# Motor_Driver.net
KiCad netlist of a schematic drawn in Altium Designer
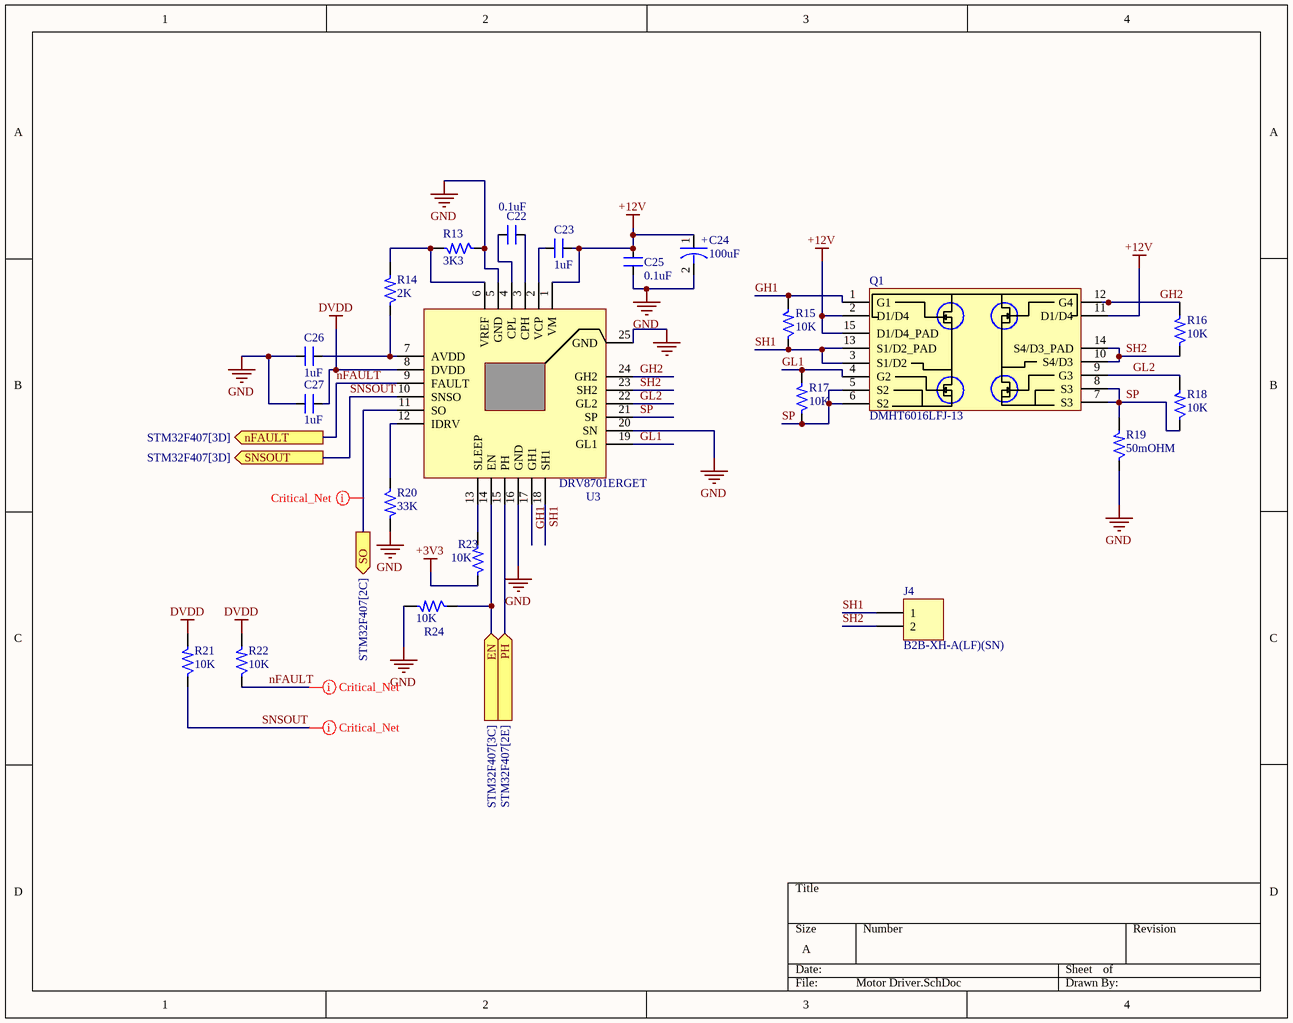
[diagram p0: Motor Driver.SchDoc]

(export (version "E")
  (design (tool "Eeschema 10.0.6"))
  (components
    (comp (ref "C22")
      (value "0.1uF")
      (footprint "CAP_0805")
      (description "0.1µF ±10% 50V Ceramic Capacitor X7R 0805 (2012 Metric)")
      (fields
        (field (name "MANUFACTURER") "Samsung")
        (field (name "MANUFACTURER PART NUMBER") "CL21B104KBCNNNC")
      )
      (libsource (lib "ESTEEMPCBLIB") (part "CAP_0.1uF-50V-10%-0805"))
    )
    (comp (ref "C23")
      (value "1uF")
      (footprint "CAP_0805")
      (description "1µF ±5% 50V Ceramic Capacitor X7R 0805 (2012 Metric)")
      (fields
        (field (name "MANUFACTURER") "Samsung")
        (field (name "MANUFACTURER PART NUMBER") "CC0805JKX7R9BB105")
      )
      (libsource (lib "ESTEEMPCBLIB") (part "CAP_1uF-50V-5%-0805"))
    )
    (comp (ref "C24")
      (value "100uF")
      (footprint "ACAP_P236_D305_H303_RAD")
      (description "100µF 25V Aluminum Electrolytic Capacitors Radial, Can - SMD 1000 Hrs @ 105°C")
      (fields
        (field (name "MANUFACTURER") "Nichicon")
        (field (name "MANUFACTURER PART NUMBER") "UWT1E101MCL1GS")
      )
      (libsource (lib "ESTEEMPCBLIB") (part "CAP-P_100uF-25V-20%-RAD"))
    )
    (comp (ref "C25")
      (value "0.1uF")
      (footprint "CAP_0805")
      (description "0.1µF ±10% 50V Ceramic Capacitor X7R 0805 (2012 Metric)")
      (fields
        (field (name "MANUFACTURER") "Samsung")
        (field (name "MANUFACTURER PART NUMBER") "CL21B104KBCNNNC")
      )
      (libsource (lib "ESTEEMPCBLIB") (part "CAP_0.1uF-50V-10%-0805"))
    )
    (comp (ref "C26")
      (value "1uF")
      (footprint "CAP_0805")
      (description "1µF ±5% 50V Ceramic Capacitor X7R 0805 (2012 Metric)")
      (fields
        (field (name "MANUFACTURER") "Samsung")
        (field (name "MANUFACTURER PART NUMBER") "CC0805JKX7R9BB105")
      )
      (libsource (lib "ESTEEMPCBLIB") (part "CAP_1uF-50V-5%-0805"))
    )
    (comp (ref "C27")
      (value "1uF")
      (footprint "CAP_0805")
      (description "1µF ±5% 50V Ceramic Capacitor X7R 0805 (2012 Metric)")
      (fields
        (field (name "MANUFACTURER") "Samsung")
        (field (name "MANUFACTURER PART NUMBER") "CC0805JKX7R9BB105")
      )
      (libsource (lib "ESTEEMPCBLIB") (part "CAP_1uF-50V-5%-0805"))
    )
    (comp (ref "J4")
      (value "B2B-XH-A(LF)(SN)")
      (footprint "CON2_100_B2B-XH-A_TH_ST")
      (description "2 Pins, 1 Row 2.54mm Pitch, Straight Connector, male")
      (fields (field (name "MANUFACTURER") "JST") (field (name "MATING PART NUMBER") "XHP-2"))
      (libsource (lib "ESTEEMPCBLIB") (part "CON-PLG_2X1-100-ST-TH"))
    )
    (comp (ref "Q1")
      (value "DMHT6016LFJ-13")
      (footprint "DFN5045-12_33_212_27X15_SMD_1")
      (description "Mosfet Array 4 N-Channel 14.8A (Ta) Surface Mount V-DFN5045-12")
      (fields (field (name "MANUFACTURER") "ON Semiconductor"))
      (libsource (lib "ESTEEMPCBLIB") (part "MOSFET-N_60V-14.8A-V-DFN5045-12"))
    )
    (comp (ref "R13")
      (value "3K3")
      (footprint "RES_0603")
      (description "3.3 kOhms ±1% 0.1W, 1/10W Chip Resistor 0603 (1608 Metric) Automotive AEC-Q200 Thick Film")
      (fields (field (name "MANUFACTURER") "Wilson") (field (name "MANUFACTURER PART NUMBER") "WR06X3301FTL"))
      (libsource (lib "ESTEEMPCBLIB") (part "RES_3.3K-0.1W-1%-0603"))
    )
    (comp (ref "R14")
      (value "2K")
      (footprint "RES_0603")
      (fields
        (field (name "MANUFACTURER") "Stackpole Electronics")
        (field (name "MANUFACTURER PART NUMBER") "RNCP0603FTD2K00")
      )
      (libsource (lib "ESTEEMPCBLIB") (part "RES_2K-0.125W-1%-0603"))
    )
    (comp (ref "R15")
      (value "10K")
      (footprint "RES_0603")
      (description "10 kOhms ±1% 0.1W, 1/10W Chip Resistor 0603 (1608 Metric) Automotive AEC-Q200 Thick Film")
      (fields (field (name "MANUFACTURER") "Walsin") (field (name "MANUFACTURER PART NUMBER") "WR06X1002FTL"))
      (libsource (lib "ESTEEMPCBLIB") (part "RES_10K-0.1W-1%-0603"))
    )
    (comp (ref "R16")
      (value "10K")
      (footprint "RES_0603")
      (description "10 kOhms ±1% 0.1W, 1/10W Chip Resistor 0603 (1608 Metric) Automotive AEC-Q200 Thick Film")
      (fields (field (name "MANUFACTURER") "Walsin") (field (name "MANUFACTURER PART NUMBER") "WR06X1002FTL"))
      (libsource (lib "ESTEEMPCBLIB") (part "RES_10K-0.1W-1%-0603"))
    )
    (comp (ref "R17")
      (value "10K")
      (footprint "RES_0603")
      (description "10 kOhms ±1% 0.1W, 1/10W Chip Resistor 0603 (1608 Metric) Automotive AEC-Q200 Thick Film")
      (fields (field (name "MANUFACTURER") "Walsin") (field (name "MANUFACTURER PART NUMBER") "WR06X1002FTL"))
      (libsource (lib "ESTEEMPCBLIB") (part "RES_10K-0.1W-1%-0603"))
    )
    (comp (ref "R18")
      (value "10K")
      (footprint "RES_0603")
      (description "10 kOhms ±1% 0.1W, 1/10W Chip Resistor 0603 (1608 Metric) Automotive AEC-Q200 Thick Film")
      (fields (field (name "MANUFACTURER") "Walsin") (field (name "MANUFACTURER PART NUMBER") "WR06X1002FTL"))
      (libsource (lib "ESTEEMPCBLIB") (part "RES_10K-0.1W-1%-0603"))
    )
    (comp (ref "R19")
      (value "50mOHM")
      (footprint "RES_2512")
      (fields
        (field (name "MANUFACTURER") "Yageo")
        (field (name "MANUFACTURER PART NUMBER") "PA2512FKF7W0R05E")
      )
      (libsource (lib "ESTEEMPCBLIB") (part "RES_50mOhm-2W-1%-2512"))
    )
    (comp (ref "R20")
      (value "33K")
      (footprint "RES_0805")
      (fields
        (field (name "MANUFACTURER") "Vishay BCcomponents")
        (field (name "MANUFACTURER PART NUMBER") "CRG0805F33K")
      )
      (libsource (lib "ESTEEMPCBLIB") (part "RES_33K-0.125W-1%-0805"))
    )
    (comp (ref "R21")
      (value "10K")
      (footprint "RES_0603")
      (description "10 kOhms ±1% 0.1W, 1/10W Chip Resistor 0603 (1608 Metric) Automotive AEC-Q200 Thick Film")
      (fields (field (name "MANUFACTURER") "Walsin") (field (name "MANUFACTURER PART NUMBER") "WR06X1002FTL"))
      (libsource (lib "ESTEEMPCBLIB") (part "RES_10K-0.1W-1%-0603"))
    )
    (comp (ref "R22")
      (value "10K")
      (footprint "RES_0603")
      (description "10 kOhms ±1% 0.1W, 1/10W Chip Resistor 0603 (1608 Metric) Automotive AEC-Q200 Thick Film")
      (fields (field (name "MANUFACTURER") "Walsin") (field (name "MANUFACTURER PART NUMBER") "WR06X1002FTL"))
      (libsource (lib "ESTEEMPCBLIB") (part "RES_10K-0.1W-1%-0603"))
    )
    (comp (ref "R23")
      (value "10K")
      (footprint "RES_0603")
      (description "10 kOhms ±1% 0.1W, 1/10W Chip Resistor 0603 (1608 Metric) Automotive AEC-Q200 Thick Film")
      (fields (field (name "MANUFACTURER") "Walsin") (field (name "MANUFACTURER PART NUMBER") "WR06X1002FTL"))
      (libsource (lib "ESTEEMPCBLIB") (part "RES_10K-0.1W-1%-0603"))
    )
    (comp (ref "R24")
      (value "10K")
      (footprint "RES_0603")
      (description "10 kOhms ±1% 0.1W, 1/10W Chip Resistor 0603 (1608 Metric) Automotive AEC-Q200 Thick Film")
      (fields (field (name "MANUFACTURER") "Walsin") (field (name "MANUFACTURER PART NUMBER") "WR06X1002FTL"))
      (libsource (lib "ESTEEMPCBLIB") (part "RES_10K-0.1W-1%-0603"))
    )
    (comp (ref "U3")
      (value "DRV8701ERGET")
      (footprint "VFQFN24_19.6_196_12X32_SMD_1")
      (description "Motor Driver Power MOSFET Parallel 24-VQFN (4x4)")
      (fields (field (name "MANUFACTURER") "Texas Instruments"))
      (libsource (lib "ESTEEMPCBLIB") (part "IC_DRV8701ERGET"))
    )
  )
  (nets
    (net (code "1") (name "+3V3") (class "Default")
      (node (ref "R23") (pin "1") (pinfunction "1_1") (pintype "passive"))
    )
    (net (code "2") (name "+12V") (class "Default")
      (node (ref "C23") (pin "2") (pinfunction "2_2") (pintype "passive"))
      (node (ref "C24") (pin "1") (pinfunction "1_1") (pintype "passive"))
      (node (ref "C25") (pin "2") (pinfunction "2_2") (pintype "passive"))
      (node (ref "Q1") (pin "11") (pinfunction "D1/D4_11") (pintype "passive"))
      (node (ref "Q1") (pin "15") (pinfunction "D1/D4_PAD_15") (pintype "passive"))
      (node (ref "Q1") (pin "2") (pinfunction "D1/D4_2") (pintype "passive"))
      (node (ref "U3") (pin "1") (pinfunction "VM_1") (pintype "passive"))
    )
    (net (code "3") (name "/EN") (class "Default")
      (node (ref "R24") (pin "1") (pinfunction "1_1") (pintype "passive"))
      (node (ref "U3") (pin "14") (pinfunction "EN_14") (pintype "passive"))
    )
    (net (code "4") (name "/GH1") (class "Default")
      (node (ref "Q1") (pin "1") (pinfunction "G1_1") (pintype "passive"))
      (node (ref "R15") (pin "2") (pinfunction "2_2") (pintype "passive"))
      (node (ref "U3") (pin "17") (pinfunction "GH1_17") (pintype "passive"))
    )
    (net (code "5") (name "/GH2") (class "Default")
      (node (ref "Q1") (pin "12") (pinfunction "G4_12") (pintype "passive"))
      (node (ref "R16") (pin "2") (pinfunction "2_2") (pintype "passive"))
      (node (ref "U3") (pin "24") (pinfunction "GH2_24") (pintype "passive"))
    )
    (net (code "6") (name "/GL1") (class "Default")
      (node (ref "Q1") (pin "4") (pinfunction "G2_4") (pintype "passive"))
      (node (ref "R17") (pin "2") (pinfunction "2_2") (pintype "passive"))
      (node (ref "U3") (pin "19") (pinfunction "GL1_19") (pintype "passive"))
    )
    (net (code "7") (name "/GL2") (class "Default")
      (node (ref "Q1") (pin "9") (pinfunction "G3_9") (pintype "passive"))
      (node (ref "R18") (pin "2") (pinfunction "2_2") (pintype "passive"))
      (node (ref "U3") (pin "22") (pinfunction "GL2_22") (pintype "passive"))
    )
    (net (code "8") (name "/PH") (class "Default")
      (node (ref "U3") (pin "15") (pinfunction "PH_15") (pintype "passive"))
    )
    (net (code "9") (name "/SH1") (class "Default")
      (node (ref "J4") (pin "1") (pinfunction "1_1") (pintype "passive"))
      (node (ref "Q1") (pin "13") (pinfunction "S1/D2_PAD_13") (pintype "passive"))
      (node (ref "Q1") (pin "3") (pinfunction "S1/D2_3") (pintype "passive"))
      (node (ref "R15") (pin "1") (pinfunction "1_1") (pintype "passive"))
      (node (ref "U3") (pin "18") (pinfunction "SH1_18") (pintype "passive"))
    )
    (net (code "10") (name "/SH2") (class "Default")
      (node (ref "J4") (pin "2") (pinfunction "2_2") (pintype "passive"))
      (node (ref "Q1") (pin "10") (pinfunction "S4/D3_10") (pintype "passive"))
      (node (ref "Q1") (pin "14") (pinfunction "S4/D3_PAD_14") (pintype "passive"))
      (node (ref "R16") (pin "1") (pinfunction "1_1") (pintype "passive"))
      (node (ref "U3") (pin "23") (pinfunction "SH2_23") (pintype "passive"))
    )
    (net (code "11") (name "/SNSOUT") (class "Default")
      (node (ref "R21") (pin "1") (pinfunction "1_1") (pintype "passive"))
      (node (ref "U3") (pin "10") (pinfunction "SNSO_10") (pintype "passive"))
    )
    (net (code "12") (name "/SO") (class "Default")
      (node (ref "U3") (pin "11") (pinfunction "SO_11") (pintype "passive"))
    )
    (net (code "13") (name "/SP") (class "Default")
      (node (ref "Q1") (pin "5") (pinfunction "S2_5") (pintype "passive"))
      (node (ref "Q1") (pin "6") (pinfunction "S2_6") (pintype "passive"))
      (node (ref "Q1") (pin "7") (pinfunction "S3_7") (pintype "passive"))
      (node (ref "Q1") (pin "8") (pinfunction "S3_8") (pintype "passive"))
      (node (ref "R17") (pin "1") (pinfunction "1_1") (pintype "passive"))
      (node (ref "R18") (pin "1") (pinfunction "1_1") (pintype "passive"))
      (node (ref "R19") (pin "2") (pinfunction "2_2") (pintype "passive"))
      (node (ref "U3") (pin "21") (pinfunction "SP_21") (pintype "passive"))
    )
    (net (code "14") (name "/nFAULT") (class "Default")
      (node (ref "R22") (pin "1") (pinfunction "1_1") (pintype "passive"))
      (node (ref "U3") (pin "9") (pinfunction "FAULT_9") (pintype "passive"))
    )
    (net (code "15") (name "DVDD") (class "Default")
      (node (ref "C27") (pin "1") (pinfunction "1_1") (pintype "passive"))
      (node (ref "R21") (pin "2") (pinfunction "2_2") (pintype "passive"))
      (node (ref "R22") (pin "2") (pinfunction "2_2") (pintype "passive"))
      (node (ref "U3") (pin "8") (pinfunction "DVDD_8") (pintype "passive"))
    )
    (net (code "16") (name "GND") (class "Default")
      (node (ref "C24") (pin "2") (pinfunction "2_2") (pintype "passive"))
      (node (ref "C25") (pin "1") (pinfunction "1_1") (pintype "passive"))
      (node (ref "C26") (pin "2") (pinfunction "2_2") (pintype "passive"))
      (node (ref "C27") (pin "2") (pinfunction "2_2") (pintype "passive"))
      (node (ref "R13") (pin "1") (pinfunction "1_1") (pintype "passive"))
      (node (ref "R19") (pin "1") (pinfunction "1_1") (pintype "passive"))
      (node (ref "R20") (pin "2") (pinfunction "2_2") (pintype "passive"))
      (node (ref "R24") (pin "2") (pinfunction "2_2") (pintype "passive"))
      (node (ref "U3") (pin "16") (pinfunction "GND_16") (pintype "passive"))
      (node (ref "U3") (pin "20") (pinfunction "SN_20") (pintype "passive"))
      (node (ref "U3") (pin "25") (pinfunction "GND_25") (pintype "passive"))
      (node (ref "U3") (pin "5") (pinfunction "GND_5") (pintype "passive"))
    )
    (net (code "17") (name "Net-(U3-AVDD)") (class "Default")
      (node (ref "C26") (pin "1") (pinfunction "1_1") (pintype "passive"))
      (node (ref "R14") (pin "1") (pinfunction "1_1") (pintype "passive"))
      (node (ref "U3") (pin "7") (pinfunction "AVDD_7") (pintype "passive"))
    )
    (net (code "18") (name "Net-(U3-CPH)") (class "Default")
      (node (ref "C22") (pin "2") (pinfunction "2_2") (pintype "passive"))
      (node (ref "U3") (pin "3") (pinfunction "CPH_3") (pintype "passive"))
    )
    (net (code "19") (name "Net-(U3-CPL)") (class "Default")
      (node (ref "C22") (pin "1") (pinfunction "1_1") (pintype "passive"))
      (node (ref "U3") (pin "4") (pinfunction "CPL_4") (pintype "passive"))
    )
    (net (code "20") (name "Net-(U3-IDRV)") (class "Default")
      (node (ref "R20") (pin "1") (pinfunction "1_1") (pintype "passive"))
      (node (ref "U3") (pin "12") (pinfunction "IDRV_12") (pintype "passive"))
    )
    (net (code "21") (name "Net-(U3-SLEEP)") (class "Default")
      (node (ref "R23") (pin "2") (pinfunction "2_2") (pintype "passive"))
      (node (ref "U3") (pin "13") (pinfunction "SLEEP_13") (pintype "passive"))
    )
    (net (code "22") (name "Net-(U3-VCP)") (class "Default")
      (node (ref "C23") (pin "1") (pinfunction "1_1") (pintype "passive"))
      (node (ref "U3") (pin "2") (pinfunction "VCP_2") (pintype "passive"))
    )
    (net (code "23") (name "Net-(U3-VREF)") (class "Default")
      (node (ref "R13") (pin "2") (pinfunction "2_2") (pintype "passive"))
      (node (ref "R14") (pin "2") (pinfunction "2_2") (pintype "passive"))
      (node (ref "U3") (pin "6") (pinfunction "VREF_6") (pintype "passive"))
    )
  )
)
